# bGeigieNanoKit.net
KiCad netlist of a schematic drawn in EAGLE
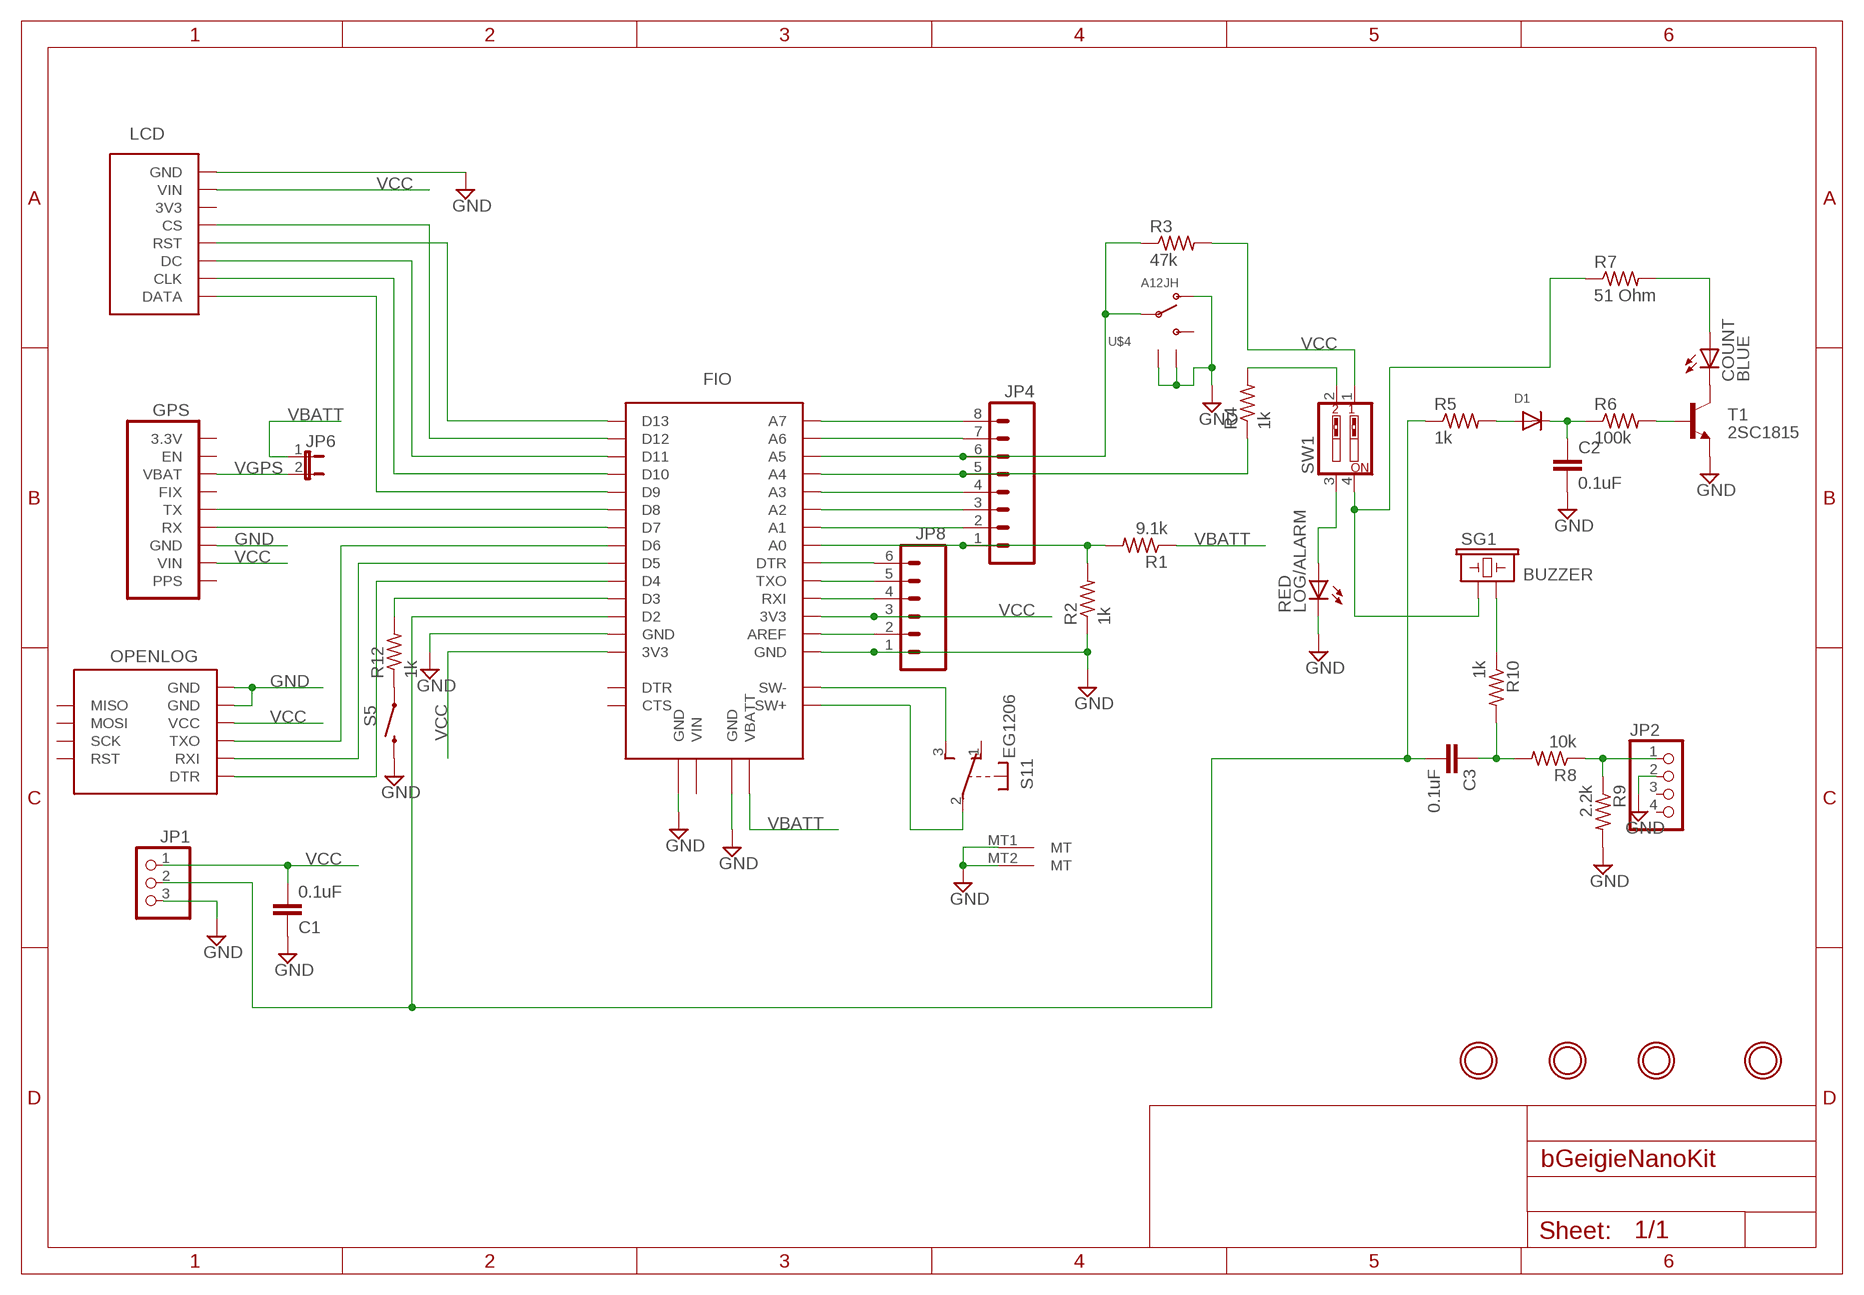
[diagram p0: schematic, sheet 1]

(export (version "E")
  (design (tool "Eeschema 10.0.6"))
  (components
    (comp (ref "C1")
      (value "0.1uF")
      (footprint "eagle-import:C025-024X044")
      (libsource (lib "eagle-import") (part "C-EU025-024X044"))
    )
    (comp (ref "C2")
      (value "0.1uF")
      (footprint "eagle-import:C025-024X044")
      (libsource (lib "eagle-import") (part "C-EU025-024X044"))
    )
    (comp (ref "C3")
      (value "0.1uF")
      (footprint "eagle-import:C025-024X044")
      (libsource (lib "eagle-import") (part "C-EU025-024X044"))
    )
    (comp (ref "COUNT")
      (value "BLUE")
      (footprint "eagle-import:LED3MM")
      (libsource (lib "eagle-import") (part "LED3MM"))
    )
    (comp (ref "D1")
      (value "DIODEDO-1N4148")
      (footprint "eagle-import:DO-1N4148")
      (libsource (lib "eagle-import") (part "DIODEDO-1N4148"))
    )
    (comp (ref "FIO")
      (value "FIO_SOCKETBOT")
      (footprint "eagle-import:FIO_V23_SOCKET_BOT")
      (libsource (lib "eagle-import") (part "FIO_SOCKETBOT"))
    )
    (comp (ref "GPS")
      (value "ULTIMATE_GPSTOP")
      (footprint "eagle-import:ULTIMATE_GPS_V3_TOP")
      (libsource (lib "eagle-import") (part "ULTIMATE_GPSTOP"))
    )
    (comp (ref "JP1")
      (value "PINHD-1X3/90")
      (footprint "eagle-import:1X03_90")
      (libsource (lib "eagle-import") (part "PINHD-1X3/90"))
    )
    (comp (ref "JP2")
      (value "HEADER-1X4ROUND")
      (footprint "eagle-import:1X04_ROUND")
      (libsource (lib "eagle-import") (part "HEADER-1X4ROUND"))
    )
    (comp (ref "JP4")
      (value "M081X08")
      (footprint "eagle-import:1X08")
      (libsource (lib "eagle-import") (part "M081X08"))
    )
    (comp (ref "JP6")
      (value "JUMPER-2SMD-NO")
      (footprint "eagle-import:SJ_2S-NO")
      (libsource (lib "eagle-import") (part "JUMPER-2SMD-NO"))
    )
    (comp (ref "JP8")
      (value "M06SIP")
      (footprint "eagle-import:1X06")
      (libsource (lib "eagle-import") (part "M06SIP"))
    )
    (comp (ref "LCD")
      (value "SSD1306_128X64_V2_LCD1.3IN_LEVER")
      (footprint "eagle-import:SSD1306_128X64_1.3IN_LCD_LEVER")
      (libsource (lib "eagle-import") (part "SSD1306_128X64_V2_LCD1.3IN_LEVER"))
    )
    (comp (ref "LOG/ALARM")
      (value "RED")
      (footprint "eagle-import:LED3MM")
      (libsource (lib "eagle-import") (part "LED3MM"))
    )
    (comp (ref "OPENLOG")
      (value "OPENLOG")
      (footprint "eagle-import:OPENLOG")
      (libsource (lib "eagle-import") (part "OPENLOG"))
    )
    (comp (ref "R1")
      (value "9.1k")
      (footprint "eagle-import:0207_10")
      (libsource (lib "eagle-import") (part "R-US_0207/10"))
    )
    (comp (ref "R2")
      (value "1k")
      (footprint "eagle-import:0207_10")
      (libsource (lib "eagle-import") (part "R-US_0207/10"))
    )
    (comp (ref "R3")
      (value "47k")
      (footprint "eagle-import:0207_10")
      (libsource (lib "eagle-import") (part "R-US_0207/10"))
    )
    (comp (ref "R4")
      (value "1k")
      (footprint "eagle-import:0207_10")
      (libsource (lib "eagle-import") (part "R-US_0207/10"))
    )
    (comp (ref "R5")
      (value "1k")
      (footprint "eagle-import:0207_10")
      (libsource (lib "eagle-import") (part "R-US_0207/10"))
    )
    (comp (ref "R6")
      (value "100k")
      (footprint "eagle-import:0207_10")
      (libsource (lib "eagle-import") (part "R-US_0207/10"))
    )
    (comp (ref "R7")
      (value "51 Ohm")
      (footprint "eagle-import:0207_10")
      (libsource (lib "eagle-import") (part "R-US_0207/10"))
    )
    (comp (ref "R8")
      (value "10k")
      (footprint "eagle-import:0207_10")
      (libsource (lib "eagle-import") (part "R-US_0207/10"))
    )
    (comp (ref "R9")
      (value "2.2k")
      (footprint "eagle-import:0207_10")
      (libsource (lib "eagle-import") (part "R-US_0207/10"))
    )
    (comp (ref "R10")
      (value "1k")
      (footprint "eagle-import:0207_10")
      (libsource (lib "eagle-import") (part "R-US_0207/10"))
    )
    (comp (ref "R12")
      (value "1k")
      (footprint "eagle-import:0207_10")
      (libsource (lib "eagle-import") (part "R-US_0207/10"))
    )
    (comp (ref "S1")
      (value "EG1206")
      (footprint "eagle-import:EG1206")
      (libsource (lib "eagle-import") (part "EG1206"))
    )
    (comp (ref "S5")
      (value "SWITCH-MOMENTARY-2PTH")
      (footprint "eagle-import:TACTILE-PTH")
      (libsource (lib "eagle-import") (part "SWITCH-MOMENTARY-2PTH"))
    )
    (comp (ref "SG1")
      (value "BUZZER")
      (footprint "eagle-import:BUZZER-12MM")
      (libsource (lib "eagle-import") (part "BUZZERPTH"))
    )
    (comp (ref "SW1")
      (value "SW_DIP-2")
      (footprint "eagle-import:EDG-02")
      (libsource (lib "eagle-import") (part "SW_DIP-2"))
    )
    (comp (ref "T1")
      (value "2SC1815")
      (footprint "eagle-import:TO92-ECB")
      (libsource (lib "eagle-import") (part "2SC1815"))
    )
    (comp (ref "U$4")
      (value "A12JH")
      (footprint "eagle-import:A12AH")
      (libsource (lib "eagle-import") (part "A12JH"))
    )
    (comp (ref "U$6")
      (value "MOUNTINGHOLE3.0THIN")
      (footprint "eagle-import:MOUNTINGHOLE_3.0_PLATEDTHIN")
      (libsource (lib "eagle-import") (part "MOUNTINGHOLE3.0THIN"))
    )
    (comp (ref "U$7")
      (value "MOUNTINGHOLE3.0THIN")
      (footprint "eagle-import:MOUNTINGHOLE_3.0_PLATEDTHIN")
      (libsource (lib "eagle-import") (part "MOUNTINGHOLE3.0THIN"))
    )
    (comp (ref "U$8")
      (value "MOUNTINGHOLE3.0THIN")
      (footprint "eagle-import:MOUNTINGHOLE_3.0_PLATEDTHIN")
      (libsource (lib "eagle-import") (part "MOUNTINGHOLE3.0THIN"))
    )
    (comp (ref "U$9")
      (value "MOUNTINGHOLE3.0THIN")
      (footprint "eagle-import:MOUNTINGHOLE_3.0_PLATEDTHIN")
      (libsource (lib "eagle-import") (part "MOUNTINGHOLE3.0THIN"))
    )
  )
  (nets
    (net (code "1") (name "/3.3V") (class "Default")
      (node (ref "GPS") (pin "JP1$9") (pinfunction "3.3V_JP1$9") (pintype "power_in"))
    )
    (net (code "2") (name "/VBATT") (class "Default")
      (node (ref "FIO") (pin "JP2$2") (pinfunction "VBATT_JP2$2") (pintype "bidirectional"))
      (node (ref "JP6") (pin "1") (pinfunction "1_1") (pintype "passive"))
      (node (ref "R1") (pin "1") (pinfunction "1_1") (pintype "passive"))
    )
    (net (code "3") (name "/VCC") (class "Default")
      (node (ref "C1") (pin "2") (pinfunction "2_2") (pintype "passive"))
      (node (ref "FIO") (pin "JP1$1") (pinfunction "3V3_JP1$1") (pintype "power_in"))
      (node (ref "FIO") (pin "JP5$3") (pinfunction "3V3_JP5$3") (pintype "power_in"))
      (node (ref "GPS") (pin "JP1$2") (pinfunction "VIN_JP1$2") (pintype "power_in"))
      (node (ref "JP1") (pin "1") (pinfunction "1_1") (pintype "passive"))
      (node (ref "JP8") (pin "3") (pinfunction "3_3") (pintype "passive"))
      (node (ref "LCD") (pin "JP1$7") (pinfunction "VIN_JP1$7") (pintype "power_in"))
      (node (ref "OPENLOG") (pin "JP1$4") (pinfunction "VCC_JP1$4") (pintype "power_in"))
      (node (ref "R3") (pin "2") (pinfunction "2_2") (pintype "passive"))
      (node (ref "SW1") (pin "1") (pinfunction "1_1") (pintype "passive"))
    )
    (net (code "4") (name "/VGPS") (class "Default")
      (node (ref "GPS") (pin "JP1$7") (pinfunction "VBAT_JP1$7") (pintype "power_in"))
      (node (ref "JP6") (pin "2") (pinfunction "2_2") (pintype "passive"))
    )
    (net (code "5") (name "GND") (class "Default")
      (node (ref "C1") (pin "1") (pinfunction "1_1") (pintype "passive"))
      (node (ref "C2") (pin "2") (pinfunction "2_2") (pintype "passive"))
      (node (ref "FIO") (pin "JP1$2") (pinfunction "GND_JP1$2") (pintype "power_in"))
      (node (ref "FIO") (pin "JP2$1") (pinfunction "GND_JP2$1") (pintype "bidirectional"))
      (node (ref "FIO") (pin "JP5$1") (pinfunction "GND_JP5$1") (pintype "power_in"))
      (node (ref "FIO") (pin "JP6$1") (pinfunction "GND_JP6$1") (pintype "bidirectional"))
      (node (ref "GPS") (pin "JP1$3") (pinfunction "GND_JP1$3") (pintype "power_in"))
      (node (ref "GPS") (pin "U$8$P$1") (pinfunction "GND_U$8$P$1") (pintype "power_in"))
      (node (ref "GPS") (pin "U$9$P$1") (pinfunction "GND_U$9$P$1") (pintype "power_in"))
      (node (ref "JP1") (pin "3") (pinfunction "3_3") (pintype "passive"))
      (node (ref "JP2") (pin "2") (pinfunction "2_2") (pintype "passive"))
      (node (ref "JP8") (pin "1") (pinfunction "1_1") (pintype "passive"))
      (node (ref "LCD") (pin "JP1$8") (pinfunction "GND_JP1$8") (pintype "power_in"))
      (node (ref "LCD") (pin "U$23$P$1") (pinfunction "GND_U$23$P$1") (pintype "power_in"))
      (node (ref "LCD") (pin "U$26$P$1") (pinfunction "GND_U$26$P$1") (pintype "power_in"))
      (node (ref "LOG/ALARM") (pin "K") (pinfunction "C_K") (pintype "passive"))
      (node (ref "OPENLOG") (pin "JP1$5") (pinfunction "GND_JP1$5") (pintype "power_in"))
      (node (ref "OPENLOG") (pin "JP1$6") (pinfunction "GND_JP1$6") (pintype "power_in"))
      (node (ref "R2") (pin "1") (pinfunction "1_1") (pintype "passive"))
      (node (ref "R9") (pin "2") (pinfunction "2_2") (pintype "passive"))
      (node (ref "S1") (pin "MT1") (pinfunction "MT_MT1") (pintype "passive"))
      (node (ref "S1") (pin "MT2") (pinfunction "MT_MT2") (pintype "passive"))
      (node (ref "S5") (pin "3") (pinfunction "2_3") (pintype "passive"))
      (node (ref "T1") (pin "E") (pinfunction "E_E") (pintype "passive"))
      (node (ref "U$4") (pin "P$1") (pinfunction "P$1_P$1") (pintype "passive"))
      (node (ref "U$4") (pin "P$4") (pinfunction "GND_P$4") (pintype "power_in"))
      (node (ref "U$4") (pin "P$5") (pinfunction "GND_P$5") (pintype "power_in"))
    )
    (net (code "6") (name "Net-(C2-Pad1)") (class "Default")
      (node (ref "C2") (pin "1") (pinfunction "1_1") (pintype "passive"))
      (node (ref "D1") (pin "C") (pinfunction "C_C") (pintype "passive"))
      (node (ref "R6") (pin "1") (pinfunction "1_1") (pintype "passive"))
    )
    (net (code "7") (name "Net-(C3-Pad1)") (class "Default")
      (node (ref "C3") (pin "1") (pinfunction "1_1") (pintype "passive"))
      (node (ref "R10") (pin "2") (pinfunction "2_2") (pintype "passive"))
      (node (ref "R8") (pin "2") (pinfunction "2_2") (pintype "passive"))
    )
    (net (code "8") (name "Net-(COUNT-C)") (class "Default")
      (node (ref "COUNT") (pin "K") (pinfunction "C_K") (pintype "passive"))
      (node (ref "T1") (pin "C") (pinfunction "C_C") (pintype "passive"))
    )
    (net (code "9") (name "Net-(COUNT-PadA)") (class "Default")
      (node (ref "COUNT") (pin "A") (pinfunction "A_A") (pintype "passive"))
      (node (ref "R7") (pin "2") (pinfunction "2_2") (pintype "passive"))
    )
    (net (code "10") (name "Net-(D1-PadA)") (class "Default")
      (node (ref "D1") (pin "A") (pinfunction "A_A") (pintype "passive"))
      (node (ref "R5") (pin "2") (pinfunction "2_2") (pintype "passive"))
    )
    (net (code "11") (name "Net-(FIO-A0)") (class "Default")
      (node (ref "FIO") (pin "JP5$7") (pinfunction "A0_JP5$7") (pintype "bidirectional"))
      (node (ref "JP4") (pin "1") (pinfunction "1_1") (pintype "passive"))
      (node (ref "R1") (pin "2") (pinfunction "2_2") (pintype "passive"))
      (node (ref "R2") (pin "2") (pinfunction "2_2") (pintype "passive"))
    )
    (net (code "12") (name "Net-(FIO-A1)") (class "Default")
      (node (ref "FIO") (pin "JP5$8") (pinfunction "A1_JP5$8") (pintype "bidirectional"))
      (node (ref "JP4") (pin "2") (pinfunction "2_2") (pintype "passive"))
    )
    (net (code "13") (name "Net-(FIO-A2)") (class "Default")
      (node (ref "FIO") (pin "JP5$9") (pinfunction "A2_JP5$9") (pintype "bidirectional"))
      (node (ref "JP4") (pin "3") (pinfunction "3_3") (pintype "passive"))
    )
    (net (code "14") (name "Net-(FIO-A3)") (class "Default")
      (node (ref "FIO") (pin "JP5$10") (pinfunction "A3_JP5$10") (pintype "bidirectional"))
      (node (ref "JP4") (pin "4") (pinfunction "4_4") (pintype "passive"))
    )
    (net (code "15") (name "Net-(FIO-A4)") (class "Default")
      (node (ref "FIO") (pin "JP5$11") (pinfunction "A4_JP5$11") (pintype "bidirectional"))
      (node (ref "JP4") (pin "5") (pinfunction "5_5") (pintype "passive"))
      (node (ref "R4") (pin "1") (pinfunction "1_1") (pintype "passive"))
    )
    (net (code "16") (name "Net-(FIO-A5)") (class "Default")
      (node (ref "FIO") (pin "JP5$12") (pinfunction "A5_JP5$12") (pintype "bidirectional"))
      (node (ref "JP4") (pin "6") (pinfunction "6_6") (pintype "passive"))
      (node (ref "R3") (pin "1") (pinfunction "1_1") (pintype "passive"))
      (node (ref "U$4") (pin "P$2") (pinfunction "P$2_P$2") (pintype "passive"))
    )
    (net (code "17") (name "Net-(FIO-A6)") (class "Default")
      (node (ref "FIO") (pin "JP5$13") (pinfunction "A6_JP5$13") (pintype "bidirectional"))
      (node (ref "JP4") (pin "7") (pinfunction "7_7") (pintype "passive"))
    )
    (net (code "18") (name "Net-(FIO-A7)") (class "Default")
      (node (ref "FIO") (pin "JP5$14") (pinfunction "A7_JP5$14") (pintype "bidirectional"))
      (node (ref "JP4") (pin "8") (pinfunction "8_8") (pintype "passive"))
    )
    (net (code "19") (name "Net-(FIO-AREF)") (class "Default")
      (node (ref "FIO") (pin "JP5$2") (pinfunction "AREF_JP5$2") (pintype "output"))
      (node (ref "JP8") (pin "2") (pinfunction "2_2") (pintype "passive"))
    )
    (net (code "20") (name "Net-(FIO-D2)") (class "Default")
      (node (ref "C3") (pin "2") (pinfunction "2_2") (pintype "passive"))
      (node (ref "FIO") (pin "JP1$3") (pinfunction "D2_JP1$3") (pintype "bidirectional"))
      (node (ref "JP1") (pin "2") (pinfunction "2_2") (pintype "passive"))
      (node (ref "R5") (pin "1") (pinfunction "1_1") (pintype "passive"))
    )
    (net (code "21") (name "Net-(FIO-D3)") (class "Default")
      (node (ref "FIO") (pin "JP1$4") (pinfunction "D3_JP1$4") (pintype "bidirectional"))
      (node (ref "R12") (pin "2") (pinfunction "2_2") (pintype "passive"))
    )
    (net (code "22") (name "Net-(FIO-D4)") (class "Default")
      (node (ref "FIO") (pin "JP1$5") (pinfunction "D4_JP1$5") (pintype "bidirectional"))
      (node (ref "OPENLOG") (pin "JP1$1") (pinfunction "DTR_JP1$1") (pintype "input"))
    )
    (net (code "23") (name "Net-(FIO-D5)") (class "Default")
      (node (ref "FIO") (pin "JP1$6") (pinfunction "D5_JP1$6") (pintype "bidirectional"))
      (node (ref "OPENLOG") (pin "JP1$2") (pinfunction "RXI_JP1$2") (pintype "input"))
    )
    (net (code "24") (name "Net-(FIO-D6)") (class "Default")
      (node (ref "FIO") (pin "JP1$7") (pinfunction "D6_JP1$7") (pintype "bidirectional"))
      (node (ref "OPENLOG") (pin "JP1$3") (pinfunction "TXO_JP1$3") (pintype "output"))
    )
    (net (code "25") (name "Net-(FIO-D7)") (class "Default")
      (node (ref "FIO") (pin "JP1$8") (pinfunction "D7_JP1$8") (pintype "bidirectional"))
      (node (ref "GPS") (pin "JP1$4") (pinfunction "RX_JP1$4") (pintype "input"))
    )
    (net (code "26") (name "Net-(FIO-D8)") (class "Default")
      (node (ref "FIO") (pin "JP1$9") (pinfunction "D8_JP1$9") (pintype "bidirectional"))
      (node (ref "GPS") (pin "JP1$5") (pinfunction "TX_JP1$5") (pintype "output"))
    )
    (net (code "27") (name "Net-(FIO-D9)") (class "Default")
      (node (ref "FIO") (pin "JP1$10") (pinfunction "D9_JP1$10") (pintype "bidirectional"))
      (node (ref "LCD") (pin "JP1$1") (pinfunction "DATA_JP1$1") (pintype "bidirectional"))
    )
    (net (code "28") (name "Net-(FIO-D10)") (class "Default")
      (node (ref "FIO") (pin "JP1$11") (pinfunction "D10_JP1$11") (pintype "bidirectional"))
      (node (ref "LCD") (pin "JP1$2") (pinfunction "CLK_JP1$2") (pintype "bidirectional"))
    )
    (net (code "29") (name "Net-(FIO-D11)") (class "Default")
      (node (ref "FIO") (pin "JP1$12") (pinfunction "D11_JP1$12") (pintype "bidirectional"))
      (node (ref "LCD") (pin "JP1$3") (pinfunction "DC_JP1$3") (pintype "bidirectional"))
    )
    (net (code "30") (name "Net-(FIO-D12)") (class "Default")
      (node (ref "FIO") (pin "JP1$13") (pinfunction "D12_JP1$13") (pintype "bidirectional"))
      (node (ref "LCD") (pin "JP1$5") (pinfunction "CS_JP1$5") (pintype "bidirectional"))
    )
    (net (code "31") (name "Net-(FIO-D13)") (class "Default")
      (node (ref "FIO") (pin "JP1$14") (pinfunction "D13_JP1$14") (pintype "bidirectional"))
      (node (ref "LCD") (pin "JP1$4") (pinfunction "RST_JP1$4") (pintype "bidirectional"))
    )
    (net (code "32") (name "Net-(FIO-DTR-PadJP5$6)") (class "Default")
      (node (ref "FIO") (pin "JP5$6") (pinfunction "DTR_JP5$6") (pintype "input"))
      (node (ref "JP8") (pin "6") (pinfunction "6_6") (pintype "passive"))
    )
    (net (code "33") (name "Net-(FIO-RXI)") (class "Default")
      (node (ref "FIO") (pin "JP5$4") (pinfunction "RXI_JP5$4") (pintype "input"))
      (node (ref "JP8") (pin "4") (pinfunction "4_4") (pintype "passive"))
    )
    (net (code "34") (name "Net-(FIO-SW+)") (class "Default")
      (node (ref "FIO") (pin "JP7$2") (pinfunction "SW+_JP7$2") (pintype "bidirectional"))
      (node (ref "S1") (pin "2") (pinfunction "P_2") (pintype "passive"))
    )
    (net (code "35") (name "Net-(FIO-SW-)") (class "Default")
      (node (ref "FIO") (pin "JP7$1") (pinfunction "SW-_JP7$1") (pintype "bidirectional"))
      (node (ref "S1") (pin "3") (pinfunction "S_3") (pintype "passive"))
    )
    (net (code "36") (name "Net-(FIO-TXO)") (class "Default")
      (node (ref "FIO") (pin "JP5$5") (pinfunction "TXO_JP5$5") (pintype "output"))
      (node (ref "JP8") (pin "5") (pinfunction "5_5") (pintype "passive"))
    )
    (net (code "37") (name "Net-(JP2-Pad1)") (class "Default")
      (node (ref "JP2") (pin "1") (pinfunction "1_1") (pintype "passive"))
      (node (ref "R8") (pin "1") (pinfunction "1_1") (pintype "passive"))
      (node (ref "R9") (pin "1") (pinfunction "1_1") (pintype "passive"))
    )
    (net (code "38") (name "Net-(LOG/ALARM-PadA)") (class "Default")
      (node (ref "LOG/ALARM") (pin "A") (pinfunction "A_A") (pintype "passive"))
      (node (ref "SW1") (pin "3") (pinfunction "3_3") (pintype "passive"))
    )
    (net (code "39") (name "Net-(R4-Pad2)") (class "Default")
      (node (ref "R4") (pin "2") (pinfunction "2_2") (pintype "passive"))
      (node (ref "SW1") (pin "2") (pinfunction "2_2") (pintype "passive"))
    )
    (net (code "40") (name "Net-(R6-Pad2)") (class "Default")
      (node (ref "R6") (pin "2") (pinfunction "2_2") (pintype "passive"))
      (node (ref "T1") (pin "B") (pinfunction "B_B") (pintype "passive"))
    )
    (net (code "41") (name "Net-(R12-Pad1)") (class "Default")
      (node (ref "R12") (pin "1") (pinfunction "1_1") (pintype "passive"))
      (node (ref "S5") (pin "1") (pinfunction "1_1") (pintype "passive"))
    )
    (net (code "42") (name "Net-(SG1-1)") (class "Default")
      (node (ref "R7") (pin "1") (pinfunction "1_1") (pintype "passive"))
      (node (ref "SG1") (pin "+") (pinfunction "1_+") (pintype "passive"))
      (node (ref "SW1") (pin "4") (pinfunction "4_4") (pintype "passive"))
    )
    (net (code "43") (name "Net-(SG1-2)") (class "Default")
      (node (ref "R10") (pin "1") (pinfunction "1_1") (pintype "passive"))
      (node (ref "SG1") (pin "-") (pinfunction "2_-") (pintype "passive"))
    )
    (net (code "44") (name "unconnected-(FIO-CTS-PadJP8$1)") (class "Default")
      (node (ref "FIO") (pin "JP8$1") (pinfunction "CTS_JP8$1") (pintype "bidirectional"))
    )
    (net (code "45") (name "unconnected-(FIO-DTR-PadJP9$1)") (class "Default")
      (node (ref "FIO") (pin "JP9$1") (pinfunction "DTR_JP9$1") (pintype "bidirectional"))
    )
    (net (code "46") (name "unconnected-(FIO-VIN-PadJP6$2)") (class "Default")
      (node (ref "FIO") (pin "JP6$2") (pinfunction "VIN_JP6$2") (pintype "bidirectional"))
    )
    (net (code "47") (name "unconnected-(GPS-EN-PadJP1$8)") (class "Default")
      (node (ref "GPS") (pin "JP1$8") (pinfunction "EN_JP1$8") (pintype "input"))
    )
    (net (code "48") (name "unconnected-(GPS-FIX-PadJP1$6)") (class "Default")
      (node (ref "GPS") (pin "JP1$6") (pinfunction "FIX_JP1$6") (pintype "output"))
    )
    (net (code "49") (name "unconnected-(GPS-PPS-PadJP1$1)") (class "Default")
      (node (ref "GPS") (pin "JP1$1") (pinfunction "PPS_JP1$1") (pintype "output"))
    )
    (net (code "50") (name "unconnected-(JP2-Pad3)") (class "Default")
      (node (ref "JP2") (pin "3") (pinfunction "3_3") (pintype "passive"))
    )
    (net (code "51") (name "unconnected-(JP2-Pad4)") (class "Default")
      (node (ref "JP2") (pin "4") (pinfunction "4_4") (pintype "passive"))
    )
    (net (code "52") (name "unconnected-(LCD-3V3-PadJP1$6)") (class "Default")
      (node (ref "LCD") (pin "JP1$6") (pinfunction "3V3_JP1$6") (pintype "bidirectional"))
    )
    (net (code "53") (name "unconnected-(OPENLOG-MISO-PadJP2$4)") (class "Default")
      (node (ref "OPENLOG") (pin "JP2$4") (pinfunction "MISO_JP2$4") (pintype "bidirectional"))
    )
    (net (code "54") (name "unconnected-(OPENLOG-MOSI-PadJP2$3)") (class "Default")
      (node (ref "OPENLOG") (pin "JP2$3") (pinfunction "MOSI_JP2$3") (pintype "bidirectional"))
    )
    (net (code "55") (name "unconnected-(OPENLOG-RST-PadJP2$1)") (class "Default")
      (node (ref "OPENLOG") (pin "JP2$1") (pinfunction "RST_JP2$1") (pintype "input"))
    )
    (net (code "56") (name "unconnected-(OPENLOG-SCK-PadJP2$2)") (class "Default")
      (node (ref "OPENLOG") (pin "JP2$2") (pinfunction "SCK_JP2$2") (pintype "bidirectional"))
    )
    (net (code "57") (name "unconnected-(S1A-O-Pad1)") (class "Default")
      (node (ref "S1") (pin "1") (pinfunction "O_1") (pintype "passive"))
    )
    (net (code "58") (name "unconnected-(U$4-PadP$3)") (class "Default")
      (node (ref "U$4") (pin "P$3") (pinfunction "P$3_P$3") (pintype "passive"))
    )
  )
)
